# Bus_Template_V3_2.net
KiCad netlist of a schematic drawn in EAGLE
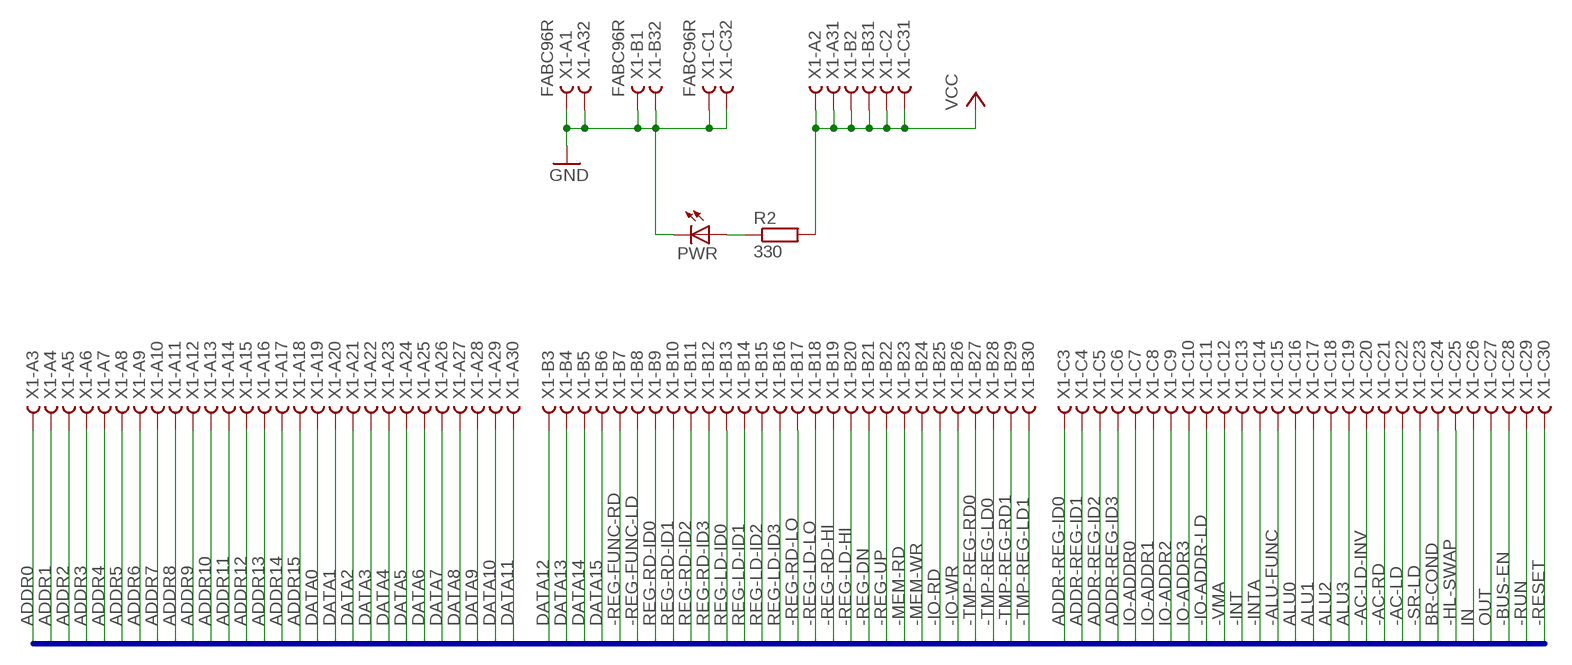
[diagram p0: schematic, sheet 1]

(export (version "E")
  (design (tool "Eeschema 10.0.6"))
  (components
    (comp (ref "PWR")
      (value "LED5MM")
      (footprint "eagle-import:LED5MM")
      (libsource (lib "eagle-import") (part "LED5MM"))
    )
    (comp (ref "R2")
      (value "330")
      (footprint "eagle-import:0207_10")
      (libsource (lib "eagle-import") (part "R0207/10"))
    )
    (comp (ref "X1")
      (value "FABC96R")
      (footprint "eagle-import:FABC96R")
      (libsource (lib "eagle-import") (part "FABC96R"))
    )
  )
  (nets
    (net (code "1") (name "/-AC-LD") (class "Default")
      (node (ref "X1") (pin "C22") (pinfunction "B_C22") (pintype "passive"))
    )
    (net (code "2") (name "/-AC-LD-INV") (class "Default")
      (node (ref "X1") (pin "C20") (pinfunction "B_C20") (pintype "passive"))
    )
    (net (code "3") (name "/-AC-RD") (class "Default")
      (node (ref "X1") (pin "C21") (pinfunction "B_C21") (pintype "passive"))
    )
    (net (code "4") (name "/-ALU-FUNC") (class "Default")
      (node (ref "X1") (pin "C15") (pinfunction "B_C15") (pintype "passive"))
    )
    (net (code "5") (name "/-BUS-EN") (class "Default")
      (node (ref "X1") (pin "C28") (pinfunction "B_C28") (pintype "passive"))
    )
    (net (code "6") (name "/-HL-SWAP") (class "Default")
      (node (ref "X1") (pin "C25") (pinfunction "B_C25") (pintype "passive"))
    )
    (net (code "7") (name "/-INT") (class "Default")
      (node (ref "X1") (pin "C13") (pinfunction "B_C13") (pintype "passive"))
    )
    (net (code "8") (name "/-INTA") (class "Default")
      (node (ref "X1") (pin "C14") (pinfunction "B_C14") (pintype "passive"))
    )
    (net (code "9") (name "/-IO-ADDR-LD") (class "Default")
      (node (ref "X1") (pin "C11") (pinfunction "B_C11") (pintype "passive"))
    )
    (net (code "10") (name "/-IO-RD") (class "Default")
      (node (ref "X1") (pin "B25") (pinfunction "B_B25") (pintype "passive"))
    )
    (net (code "11") (name "/-IO-WR") (class "Default")
      (node (ref "X1") (pin "B26") (pinfunction "B_B26") (pintype "passive"))
    )
    (net (code "12") (name "/-MEM-RD") (class "Default")
      (node (ref "X1") (pin "B23") (pinfunction "B_B23") (pintype "passive"))
    )
    (net (code "13") (name "/-MEM-WR") (class "Default")
      (node (ref "X1") (pin "B24") (pinfunction "B_B24") (pintype "passive"))
    )
    (net (code "14") (name "/-REG-DN") (class "Default")
      (node (ref "X1") (pin "B21") (pinfunction "B_B21") (pintype "passive"))
    )
    (net (code "15") (name "/-REG-FUNC-LD") (class "Default")
      (node (ref "X1") (pin "B8") (pinfunction "B_B8") (pintype "passive"))
    )
    (net (code "16") (name "/-REG-FUNC-RD") (class "Default")
      (node (ref "X1") (pin "B7") (pinfunction "B_B7") (pintype "passive"))
    )
    (net (code "17") (name "/-REG-LD-HI") (class "Default")
      (node (ref "X1") (pin "B20") (pinfunction "B_B20") (pintype "passive"))
    )
    (net (code "18") (name "/-REG-LD-LO") (class "Default")
      (node (ref "X1") (pin "B18") (pinfunction "B_B18") (pintype "passive"))
    )
    (net (code "19") (name "/-REG-RD-HI") (class "Default")
      (node (ref "X1") (pin "B19") (pinfunction "B_B19") (pintype "passive"))
    )
    (net (code "20") (name "/-REG-RD-LO") (class "Default")
      (node (ref "X1") (pin "B17") (pinfunction "B_B17") (pintype "passive"))
    )
    (net (code "21") (name "/-REG-UP") (class "Default")
      (node (ref "X1") (pin "B22") (pinfunction "B_B22") (pintype "passive"))
    )
    (net (code "22") (name "/-RESET") (class "Default")
      (node (ref "X1") (pin "C30") (pinfunction "B_C30") (pintype "passive"))
    )
    (net (code "23") (name "/-RUN") (class "Default")
      (node (ref "X1") (pin "C29") (pinfunction "B_C29") (pintype "passive"))
    )
    (net (code "24") (name "/-SR-LD") (class "Default")
      (node (ref "X1") (pin "C23") (pinfunction "B_C23") (pintype "passive"))
    )
    (net (code "25") (name "/-TMP-REG-LD0") (class "Default")
      (node (ref "X1") (pin "B28") (pinfunction "B_B28") (pintype "passive"))
    )
    (net (code "26") (name "/-TMP-REG-LD1") (class "Default")
      (node (ref "X1") (pin "B30") (pinfunction "B_B30") (pintype "passive"))
    )
    (net (code "27") (name "/-TMP-REG-RD0") (class "Default")
      (node (ref "X1") (pin "B27") (pinfunction "B_B27") (pintype "passive"))
    )
    (net (code "28") (name "/-TMP-REG-RD1") (class "Default")
      (node (ref "X1") (pin "B29") (pinfunction "B_B29") (pintype "passive"))
    )
    (net (code "29") (name "/-VMA") (class "Default")
      (node (ref "X1") (pin "C12") (pinfunction "B_C12") (pintype "passive"))
    )
    (net (code "30") (name "/ADDR-REG-ID0") (class "Default")
      (node (ref "X1") (pin "C3") (pinfunction "B_C3") (pintype "passive"))
    )
    (net (code "31") (name "/ADDR-REG-ID1") (class "Default")
      (node (ref "X1") (pin "C4") (pinfunction "B_C4") (pintype "passive"))
    )
    (net (code "32") (name "/ADDR-REG-ID2") (class "Default")
      (node (ref "X1") (pin "C5") (pinfunction "B_C5") (pintype "passive"))
    )
    (net (code "33") (name "/ADDR-REG-ID3") (class "Default")
      (node (ref "X1") (pin "C6") (pinfunction "B_C6") (pintype "passive"))
    )
    (net (code "34") (name "/ADDR0") (class "Default")
      (node (ref "X1") (pin "A3") (pinfunction "B_A3") (pintype "passive"))
    )
    (net (code "35") (name "/ADDR1") (class "Default")
      (node (ref "X1") (pin "A4") (pinfunction "B_A4") (pintype "passive"))
    )
    (net (code "36") (name "/ADDR2") (class "Default")
      (node (ref "X1") (pin "A5") (pinfunction "B_A5") (pintype "passive"))
    )
    (net (code "37") (name "/ADDR3") (class "Default")
      (node (ref "X1") (pin "A6") (pinfunction "B_A6") (pintype "passive"))
    )
    (net (code "38") (name "/ADDR4") (class "Default")
      (node (ref "X1") (pin "A7") (pinfunction "B_A7") (pintype "passive"))
    )
    (net (code "39") (name "/ADDR5") (class "Default")
      (node (ref "X1") (pin "A8") (pinfunction "B_A8") (pintype "passive"))
    )
    (net (code "40") (name "/ADDR6") (class "Default")
      (node (ref "X1") (pin "A9") (pinfunction "B_A9") (pintype "passive"))
    )
    (net (code "41") (name "/ADDR7") (class "Default")
      (node (ref "X1") (pin "A10") (pinfunction "B_A10") (pintype "passive"))
    )
    (net (code "42") (name "/ADDR8") (class "Default")
      (node (ref "X1") (pin "A11") (pinfunction "B_A11") (pintype "passive"))
    )
    (net (code "43") (name "/ADDR9") (class "Default")
      (node (ref "X1") (pin "A12") (pinfunction "B_A12") (pintype "passive"))
    )
    (net (code "44") (name "/ADDR10") (class "Default")
      (node (ref "X1") (pin "A13") (pinfunction "B_A13") (pintype "passive"))
    )
    (net (code "45") (name "/ADDR11") (class "Default")
      (node (ref "X1") (pin "A14") (pinfunction "B_A14") (pintype "passive"))
    )
    (net (code "46") (name "/ADDR12") (class "Default")
      (node (ref "X1") (pin "A15") (pinfunction "B_A15") (pintype "passive"))
    )
    (net (code "47") (name "/ADDR13") (class "Default")
      (node (ref "X1") (pin "A16") (pinfunction "B_A16") (pintype "passive"))
    )
    (net (code "48") (name "/ADDR14") (class "Default")
      (node (ref "X1") (pin "A17") (pinfunction "B_A17") (pintype "passive"))
    )
    (net (code "49") (name "/ADDR15") (class "Default")
      (node (ref "X1") (pin "A18") (pinfunction "B_A18") (pintype "passive"))
    )
    (net (code "50") (name "/ALU0") (class "Default")
      (node (ref "X1") (pin "C16") (pinfunction "B_C16") (pintype "passive"))
    )
    (net (code "51") (name "/ALU1") (class "Default")
      (node (ref "X1") (pin "C17") (pinfunction "B_C17") (pintype "passive"))
    )
    (net (code "52") (name "/ALU2") (class "Default")
      (node (ref "X1") (pin "C18") (pinfunction "B_C18") (pintype "passive"))
    )
    (net (code "53") (name "/ALU3") (class "Default")
      (node (ref "X1") (pin "C19") (pinfunction "B_C19") (pintype "passive"))
    )
    (net (code "54") (name "/BR-COND") (class "Default")
      (node (ref "X1") (pin "C24") (pinfunction "B_C24") (pintype "passive"))
    )
    (net (code "55") (name "/DATA0") (class "Default")
      (node (ref "X1") (pin "A19") (pinfunction "B_A19") (pintype "passive"))
    )
    (net (code "56") (name "/DATA1") (class "Default")
      (node (ref "X1") (pin "A20") (pinfunction "B_A20") (pintype "passive"))
    )
    (net (code "57") (name "/DATA2") (class "Default")
      (node (ref "X1") (pin "A21") (pinfunction "B_A21") (pintype "passive"))
    )
    (net (code "58") (name "/DATA3") (class "Default")
      (node (ref "X1") (pin "A22") (pinfunction "B_A22") (pintype "passive"))
    )
    (net (code "59") (name "/DATA4") (class "Default")
      (node (ref "X1") (pin "A23") (pinfunction "B_A23") (pintype "passive"))
    )
    (net (code "60") (name "/DATA5") (class "Default")
      (node (ref "X1") (pin "A24") (pinfunction "B_A24") (pintype "passive"))
    )
    (net (code "61") (name "/DATA6") (class "Default")
      (node (ref "X1") (pin "A25") (pinfunction "B_A25") (pintype "passive"))
    )
    (net (code "62") (name "/DATA7") (class "Default")
      (node (ref "X1") (pin "A26") (pinfunction "B_A26") (pintype "passive"))
    )
    (net (code "63") (name "/DATA8") (class "Default")
      (node (ref "X1") (pin "A27") (pinfunction "B_A27") (pintype "passive"))
    )
    (net (code "64") (name "/DATA9") (class "Default")
      (node (ref "X1") (pin "A28") (pinfunction "B_A28") (pintype "passive"))
    )
    (net (code "65") (name "/DATA10") (class "Default")
      (node (ref "X1") (pin "A29") (pinfunction "B_A29") (pintype "passive"))
    )
    (net (code "66") (name "/DATA11") (class "Default")
      (node (ref "X1") (pin "A30") (pinfunction "B_A30") (pintype "passive"))
    )
    (net (code "67") (name "/DATA12") (class "Default")
      (node (ref "X1") (pin "B3") (pinfunction "B_B3") (pintype "passive"))
    )
    (net (code "68") (name "/DATA13") (class "Default")
      (node (ref "X1") (pin "B4") (pinfunction "B_B4") (pintype "passive"))
    )
    (net (code "69") (name "/DATA14") (class "Default")
      (node (ref "X1") (pin "B5") (pinfunction "B_B5") (pintype "passive"))
    )
    (net (code "70") (name "/DATA15") (class "Default")
      (node (ref "X1") (pin "B6") (pinfunction "B_B6") (pintype "passive"))
    )
    (net (code "71") (name "/IN") (class "Default")
      (node (ref "X1") (pin "C26") (pinfunction "B_C26") (pintype "passive"))
    )
    (net (code "72") (name "/IO-ADDR0") (class "Default")
      (node (ref "X1") (pin "C7") (pinfunction "B_C7") (pintype "passive"))
    )
    (net (code "73") (name "/IO-ADDR1") (class "Default")
      (node (ref "X1") (pin "C8") (pinfunction "B_C8") (pintype "passive"))
    )
    (net (code "74") (name "/IO-ADDR2") (class "Default")
      (node (ref "X1") (pin "C9") (pinfunction "B_C9") (pintype "passive"))
    )
    (net (code "75") (name "/IO-ADDR3") (class "Default")
      (node (ref "X1") (pin "C10") (pinfunction "B_C10") (pintype "passive"))
    )
    (net (code "76") (name "/OUT") (class "Default")
      (node (ref "X1") (pin "C27") (pinfunction "B_C27") (pintype "passive"))
    )
    (net (code "77") (name "/REG-LD-ID0") (class "Default")
      (node (ref "X1") (pin "B13") (pinfunction "B_B13") (pintype "passive"))
    )
    (net (code "78") (name "/REG-LD-ID1") (class "Default")
      (node (ref "X1") (pin "B14") (pinfunction "B_B14") (pintype "passive"))
    )
    (net (code "79") (name "/REG-LD-ID2") (class "Default")
      (node (ref "X1") (pin "B15") (pinfunction "B_B15") (pintype "passive"))
    )
    (net (code "80") (name "/REG-LD-ID3") (class "Default")
      (node (ref "X1") (pin "B16") (pinfunction "B_B16") (pintype "passive"))
    )
    (net (code "81") (name "/REG-RD-ID0") (class "Default")
      (node (ref "X1") (pin "B9") (pinfunction "B_B9") (pintype "passive"))
    )
    (net (code "82") (name "/REG-RD-ID1") (class "Default")
      (node (ref "X1") (pin "B10") (pinfunction "B_B10") (pintype "passive"))
    )
    (net (code "83") (name "/REG-RD-ID2") (class "Default")
      (node (ref "X1") (pin "B11") (pinfunction "B_B11") (pintype "passive"))
    )
    (net (code "84") (name "/REG-RD-ID3") (class "Default")
      (node (ref "X1") (pin "B12") (pinfunction "B_B12") (pintype "passive"))
    )
    (net (code "85") (name "GND") (class "Default")
      (node (ref "PWR") (pin "K") (pinfunction "C_K") (pintype "passive"))
      (node (ref "X1") (pin "A1") (pinfunction "B_A1") (pintype "passive"))
      (node (ref "X1") (pin "A32") (pinfunction "B_A32") (pintype "passive"))
      (node (ref "X1") (pin "B1") (pinfunction "B_B1") (pintype "passive"))
      (node (ref "X1") (pin "B32") (pinfunction "B_B32") (pintype "passive"))
      (node (ref "X1") (pin "C1") (pinfunction "B_C1") (pintype "passive"))
      (node (ref "X1") (pin "C32") (pinfunction "B_C32") (pintype "passive"))
    )
    (net (code "86") (name "Net-(PWR-PadA)") (class "Default")
      (node (ref "PWR") (pin "A") (pinfunction "A_A") (pintype "passive"))
      (node (ref "R2") (pin "1") (pinfunction "1_1") (pintype "passive"))
    )
    (net (code "87") (name "VCC") (class "Default")
      (node (ref "R2") (pin "2") (pinfunction "2_2") (pintype "passive"))
      (node (ref "X1") (pin "A2") (pinfunction "B_A2") (pintype "passive"))
      (node (ref "X1") (pin "A31") (pinfunction "B_A31") (pintype "passive"))
      (node (ref "X1") (pin "B2") (pinfunction "B_B2") (pintype "passive"))
      (node (ref "X1") (pin "B31") (pinfunction "B_B31") (pintype "passive"))
      (node (ref "X1") (pin "C2") (pinfunction "B_C2") (pintype "passive"))
      (node (ref "X1") (pin "C31") (pinfunction "B_C31") (pintype "passive"))
    )
  )
)
